# Adafruit_Feather_RP2040_DVI.net
KiCad netlist of a schematic drawn in EAGLE
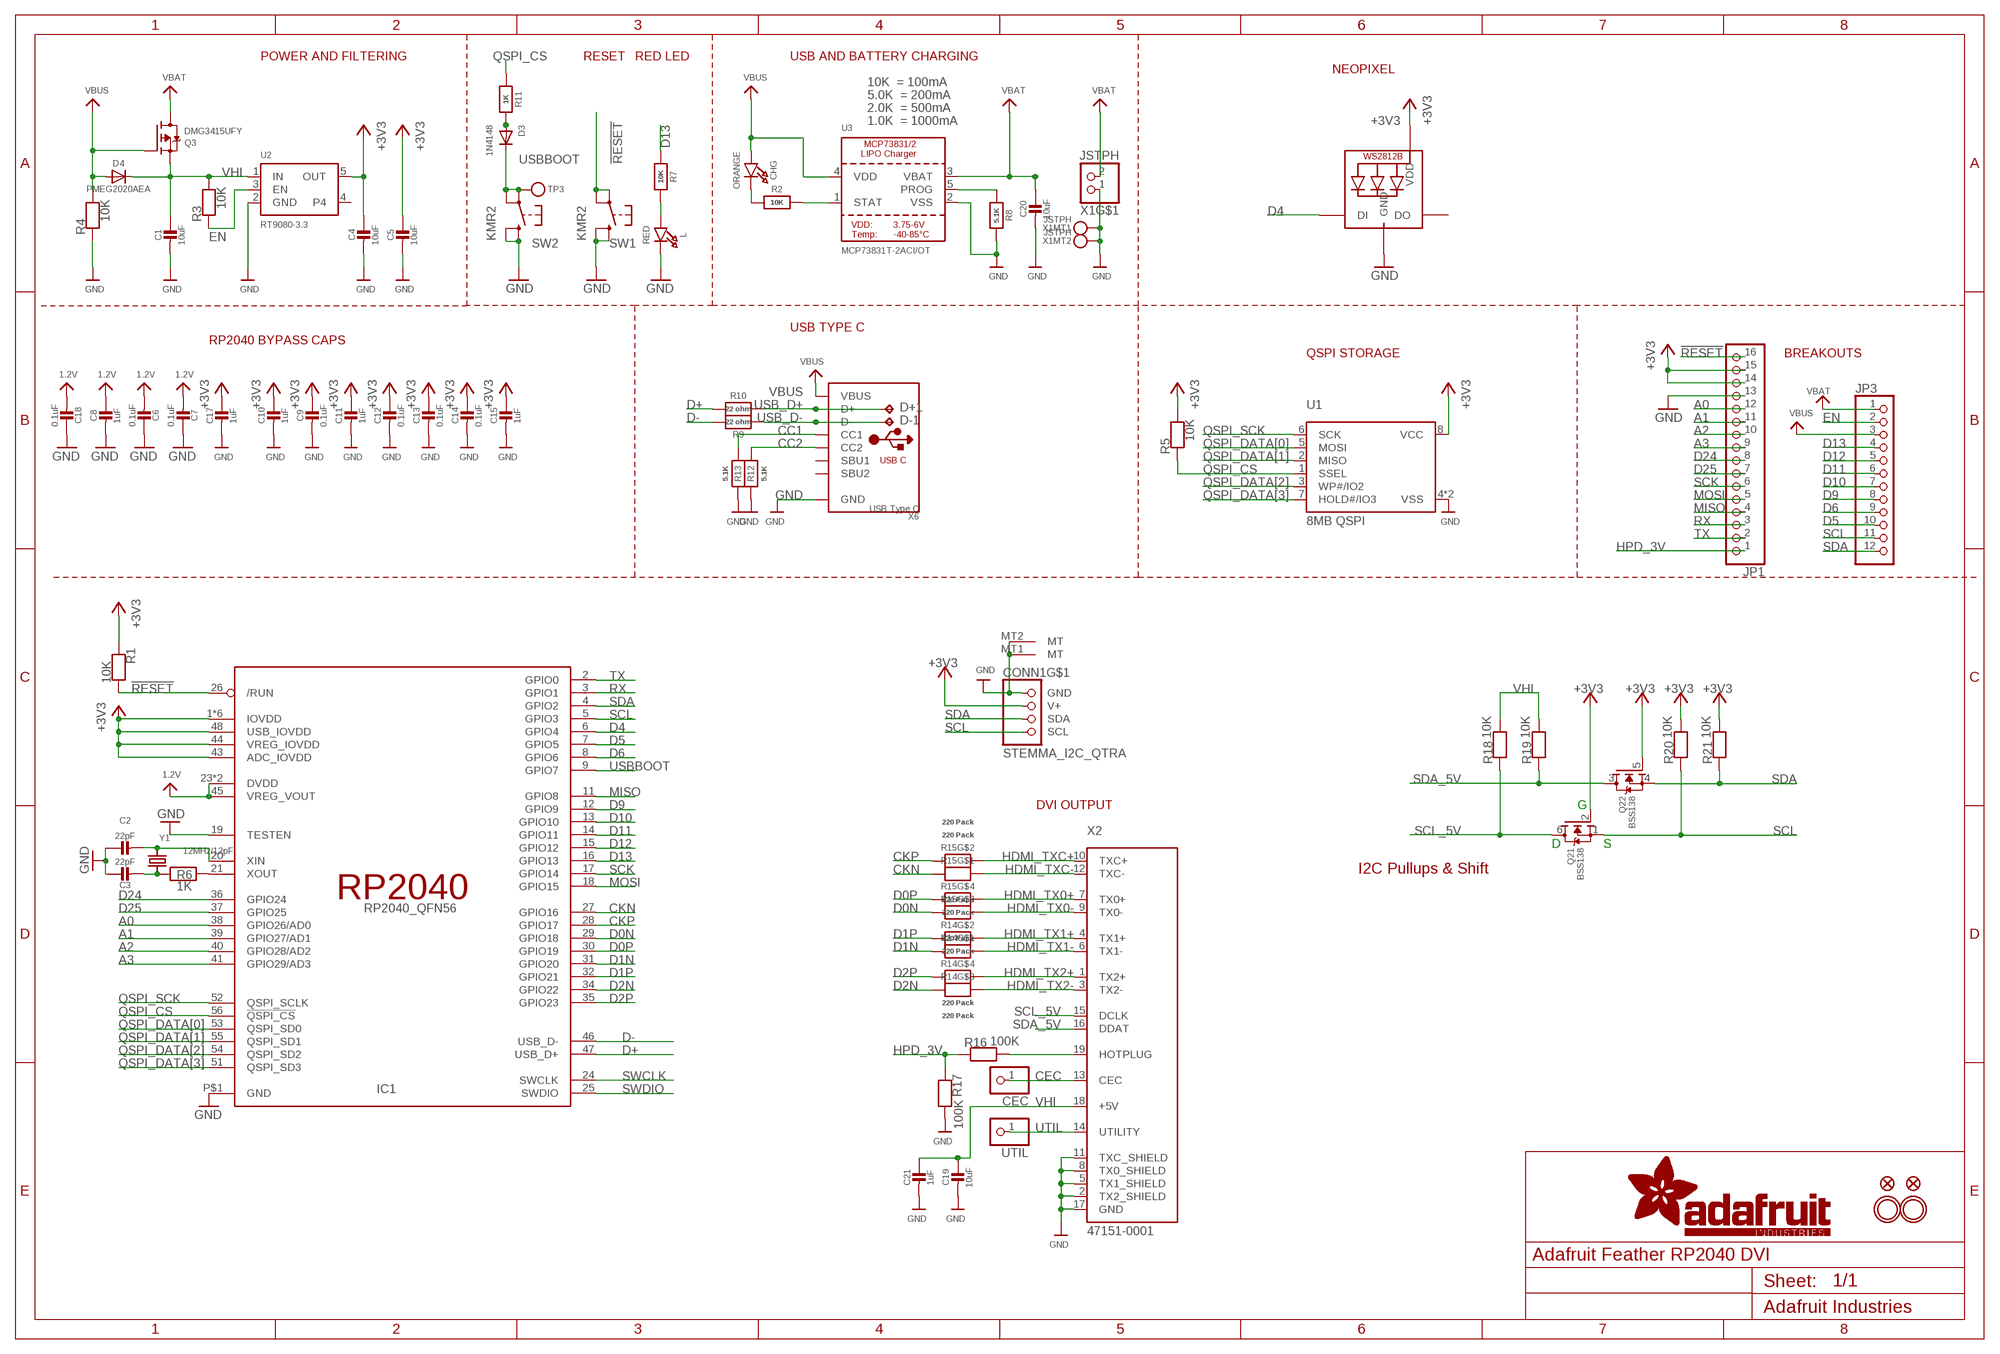
[diagram p0: schematic, sheet 1]

(export (version "E")
  (design (tool "Eeschema 10.0.6"))
  (components
    (comp (ref "C1")
      (value "10uF")
      (footprint "eagle-import:0805-NO")
      (libsource (lib "eagle-import") (part "CAP_CERAMIC0805-NOOUTLINE"))
    )
    (comp (ref "C2")
      (value "22pF")
      (footprint "eagle-import:_0402NO")
      (libsource (lib "eagle-import") (part "CAP_CERAMIC_0402NO"))
    )
    (comp (ref "C3")
      (value "22pF")
      (footprint "eagle-import:_0402NO")
      (libsource (lib "eagle-import") (part "CAP_CERAMIC_0402NO"))
    )
    (comp (ref "C4")
      (value "10uF")
      (footprint "eagle-import:0805-NO")
      (fields (field (name "REV") "A"))
      (libsource (lib "eagle-import") (part "CAP_CERAMIC0805-NOOUTLINE"))
    )
    (comp (ref "C5")
      (value "10uF")
      (footprint "eagle-import:0805-NO")
      (libsource (lib "eagle-import") (part "CAP_CERAMIC0805-NOOUTLINE"))
    )
    (comp (ref "C6")
      (value "0.1uF")
      (footprint "eagle-import:_0402NO")
      (libsource (lib "eagle-import") (part "CAP_CERAMIC_0402NO"))
    )
    (comp (ref "C7")
      (value "0.1uF")
      (footprint "eagle-import:_0402NO")
      (libsource (lib "eagle-import") (part "CAP_CERAMIC_0402NO"))
    )
    (comp (ref "C8")
      (value "1uF")
      (footprint "eagle-import:_0402NO")
      (libsource (lib "eagle-import") (part "CAP_CERAMIC_0402NO"))
    )
    (comp (ref "C9")
      (value "0.1uF")
      (footprint "eagle-import:_0402NO")
      (libsource (lib "eagle-import") (part "CAP_CERAMIC_0402NO"))
    )
    (comp (ref "C10")
      (value "1uF")
      (footprint "eagle-import:_0402NO")
      (libsource (lib "eagle-import") (part "CAP_CERAMIC_0402NO"))
    )
    (comp (ref "C11")
      (value "1uF")
      (footprint "eagle-import:_0402NO")
      (libsource (lib "eagle-import") (part "CAP_CERAMIC_0402NO"))
    )
    (comp (ref "C12")
      (value "0.1uF")
      (footprint "eagle-import:_0402NO")
      (libsource (lib "eagle-import") (part "CAP_CERAMIC_0402NO"))
    )
    (comp (ref "C13")
      (value "0.1uF")
      (footprint "eagle-import:_0402NO")
      (libsource (lib "eagle-import") (part "CAP_CERAMIC_0402NO"))
    )
    (comp (ref "C14")
      (value "0.1uF")
      (footprint "eagle-import:_0402NO")
      (libsource (lib "eagle-import") (part "CAP_CERAMIC_0402NO"))
    )
    (comp (ref "C15")
      (value "1uF")
      (footprint "eagle-import:_0402NO")
      (libsource (lib "eagle-import") (part "CAP_CERAMIC_0402NO"))
    )
    (comp (ref "C17")
      (value "1uF")
      (footprint "eagle-import:_0402NO")
      (libsource (lib "eagle-import") (part "CAP_CERAMIC_0402NO"))
    )
    (comp (ref "C18")
      (value "0.1uF")
      (footprint "eagle-import:_0402NO")
      (libsource (lib "eagle-import") (part "CAP_CERAMIC_0402NO"))
    )
    (comp (ref "C19")
      (value "10uF")
      (footprint "eagle-import:0805-NO")
      (fields (field (name "REV") "A"))
      (libsource (lib "eagle-import") (part "CAP_CERAMIC0805-NOOUTLINE"))
    )
    (comp (ref "C20")
      (value "10uF")
      (footprint "eagle-import:0805-NO")
      (libsource (lib "eagle-import") (part "CAP_CERAMIC0805-NOOUTLINE"))
    )
    (comp (ref "C21")
      (value "1uF")
      (footprint "eagle-import:_0402NO")
      (libsource (lib "eagle-import") (part "CAP_CERAMIC_0402NO"))
    )
    (comp (ref "CEC")
      (value "HEADER-1X1ROUND")
      (footprint "eagle-import:1X01_ROUND")
      (libsource (lib "eagle-import") (part "HEADER-1X1ROUND"))
    )
    (comp (ref "CHG")
      (value "ORANGE")
      (footprint "eagle-import:CHIPLED_0603_NOOUTLINE")
      (libsource (lib "eagle-import") (part "LED0603_NOOUTLINE"))
    )
    (comp (ref "CONN1")
      (value "STEMMA_I2C_QTRA")
      (footprint "eagle-import:JST_SH4_RA")
      (libsource (lib "eagle-import") (part "STEMMA_I2C_QTRA"))
    )
    (comp (ref "D+1")
      (value "TPB1,27")
      (footprint "eagle-import:B1,27")
      (libsource (lib "eagle-import") (part "TPB1,27"))
    )
    (comp (ref "D-1")
      (value "TPB1,27")
      (footprint "eagle-import:B1,27")
      (libsource (lib "eagle-import") (part "TPB1,27"))
    )
    (comp (ref "D3")
      (value "1N4148")
      (footprint "eagle-import:SOD-323F")
      (libsource (lib "eagle-import") (part "DIODESOD-323F"))
    )
    (comp (ref "D4")
      (value "PMEG2020AEA")
      (footprint "eagle-import:SOD-323F")
      (libsource (lib "eagle-import") (part "DIODESOD-323F"))
    )
    (comp (ref "IC1")
      (value "RP2040_QFN56")
      (footprint "eagle-import:QFN56_7MM_REDUCEDEPAD")
      (libsource (lib "eagle-import") (part "RP2040_QFN56"))
    )
    (comp (ref "JP1")
      (value "HEADER-1X16ROUND")
      (footprint "eagle-import:1X16_ROUND")
      (libsource (lib "eagle-import") (part "HEADER-1X16ROUND"))
    )
    (comp (ref "JP3")
      (value "HEADER-1X12")
      (footprint "eagle-import:1X12_ROUND")
      (libsource (lib "eagle-import") (part "HEADER-1X12"))
    )
    (comp (ref "L")
      (value "RED")
      (footprint "eagle-import:CHIPLED_0603_NOOUTLINE")
      (libsource (lib "eagle-import") (part "LED0603_NOOUTLINE"))
    )
    (comp (ref "LED1")
      (value "WS2812B_SK6805_1515")
      (footprint "eagle-import:SK6805_1515")
      (libsource (lib "eagle-import") (part "WS2812B_SK6805_1515"))
    )
    (comp (ref "Q2")
      (value "BSS138")
      (footprint "eagle-import:SOT363")
      (libsource (lib "eagle-import") (part "MOSFET-N_DUAL"))
    )
    (comp (ref "Q3")
      (value "DMG3415UFY")
      (footprint "eagle-import:DFN2015-3")
      (libsource (lib "eagle-import") (part "MOSFET-P_DFN2015"))
    )
    (comp (ref "R1")
      (value "10K")
      (footprint "eagle-import:_0402NO")
      (libsource (lib "eagle-import") (part "RESISTOR_0402NO"))
    )
    (comp (ref "R2")
      (value "10K")
      (footprint "eagle-import:_0402NO")
      (libsource (lib "eagle-import") (part "RESISTOR_0402NO"))
    )
    (comp (ref "R3")
      (value "10K")
      (footprint "eagle-import:_0402NO")
      (libsource (lib "eagle-import") (part "RESISTOR_0402NO"))
    )
    (comp (ref "R4")
      (value "10K")
      (footprint "eagle-import:_0402NO")
      (libsource (lib "eagle-import") (part "RESISTOR_0402NO"))
    )
    (comp (ref "R5")
      (value "10K")
      (footprint "eagle-import:_0402NO")
      (libsource (lib "eagle-import") (part "RESISTOR_0402NO"))
    )
    (comp (ref "R6")
      (value "1K")
      (footprint "eagle-import:_0402NO")
      (libsource (lib "eagle-import") (part "RESISTOR_0402NO"))
    )
    (comp (ref "R7")
      (value "10K")
      (footprint "eagle-import:_0402NO")
      (libsource (lib "eagle-import") (part "RESISTOR_0402NO"))
    )
    (comp (ref "R8")
      (value "5.1K")
      (footprint "eagle-import:_0402NO")
      (libsource (lib "eagle-import") (part "RESISTOR_0402NO"))
    )
    (comp (ref "R9")
      (value "22 ohm")
      (footprint "eagle-import:_0402NO")
      (libsource (lib "eagle-import") (part "RESISTOR_0402NO"))
    )
    (comp (ref "R10")
      (value "22 ohm")
      (footprint "eagle-import:_0402NO")
      (libsource (lib "eagle-import") (part "RESISTOR_0402NO"))
    )
    (comp (ref "R11")
      (value "1K")
      (footprint "eagle-import:_0402NO")
      (libsource (lib "eagle-import") (part "RESISTOR_0402NO"))
    )
    (comp (ref "R12")
      (value "5.1K")
      (footprint "eagle-import:_0402NO")
      (libsource (lib "eagle-import") (part "RESISTOR_0402NO"))
    )
    (comp (ref "R13")
      (value "5.1K")
      (footprint "eagle-import:_0402NO")
      (libsource (lib "eagle-import") (part "RESISTOR_0402NO"))
    )
    (comp (ref "R14")
      (value "220 Pack")
      (footprint "eagle-import:RESPACK_4X0603")
      (libsource (lib "eagle-import") (part "RESISTOR_4PACK"))
    )
    (comp (ref "R15")
      (value "220 Pack")
      (footprint "eagle-import:RESPACK_4X0603")
      (libsource (lib "eagle-import") (part "RESISTOR_4PACK"))
    )
    (comp (ref "R16")
      (value "100K")
      (footprint "eagle-import:_0402NO")
      (libsource (lib "eagle-import") (part "RESISTOR_0402NO"))
    )
    (comp (ref "R17")
      (value "100K")
      (footprint "eagle-import:_0402NO")
      (libsource (lib "eagle-import") (part "RESISTOR_0402NO"))
    )
    (comp (ref "R18")
      (value "10K")
      (footprint "eagle-import:_0402NO")
      (libsource (lib "eagle-import") (part "RESISTOR_0402NO"))
    )
    (comp (ref "R19")
      (value "10K")
      (footprint "eagle-import:_0402NO")
      (libsource (lib "eagle-import") (part "RESISTOR_0402NO"))
    )
    (comp (ref "R20")
      (value "10K")
      (footprint "eagle-import:_0402NO")
      (libsource (lib "eagle-import") (part "RESISTOR_0402NO"))
    )
    (comp (ref "R21")
      (value "10K")
      (footprint "eagle-import:_0402NO")
      (libsource (lib "eagle-import") (part "RESISTOR_0402NO"))
    )
    (comp (ref "SW1")
      (value "KMR2")
      (footprint "eagle-import:BTN_RKB2_4.6X2.8")
      (libsource (lib "eagle-import") (part "SWITCH_TACT_SMT_RKB2"))
    )
    (comp (ref "SW2")
      (value "KMR2")
      (footprint "eagle-import:BTN_RKB2_4.6X2.8")
      (libsource (lib "eagle-import") (part "SWITCH_TACT_SMT_RKB2"))
    )
    (comp (ref "TP3")
      (value "TESTPOINTROUND1.5MMNO")
      (footprint "eagle-import:TESTPOINT_ROUND_1.5MM_NO")
      (libsource (lib "eagle-import") (part "TESTPOINTROUND1.5MMNO"))
    )
    (comp (ref "U$31")
      (value "MOUNTINGHOLE2.5")
      (footprint "eagle-import:MOUNTINGHOLE_2.5_PLATED")
      (libsource (lib "eagle-import") (part "MOUNTINGHOLE2.5"))
    )
    (comp (ref "U$32")
      (value "MOUNTINGHOLE2.5")
      (footprint "eagle-import:MOUNTINGHOLE_2.5_PLATED")
      (libsource (lib "eagle-import") (part "MOUNTINGHOLE2.5"))
    )
    (comp (ref "U$34")
      (value "FIDUCIAL_1MM")
      (footprint "eagle-import:FIDUCIAL_1MM")
      (libsource (lib "eagle-import") (part "FIDUCIAL_1MM"))
    )
    (comp (ref "U$35")
      (value "FIDUCIAL_1MM")
      (footprint "eagle-import:FIDUCIAL_1MM")
      (libsource (lib "eagle-import") (part "FIDUCIAL_1MM"))
    )
    (comp (ref "U1")
      (value "8MB QSPI")
      (footprint "eagle-import:USON8_4X4")
      (libsource (lib "eagle-import") (part "SPIFLASH_8PIN_4X4"))
    )
    (comp (ref "U2")
      (value "RT9080-3.3")
      (footprint "eagle-import:SOT23-5")
      (fields (field (name "JLC_ROTATION") "0"))
      (libsource (lib "eagle-import") (part "VREG_SOT23-5"))
    )
    (comp (ref "U3")
      (value "MCP73831T-2ACI/OT")
      (footprint "eagle-import:SOT23-5")
      (libsource (lib "eagle-import") (part "MCP73831/2"))
    )
    (comp (ref "UTIL")
      (value "HEADER-1X1ROUND")
      (footprint "eagle-import:1X01_ROUND")
      (libsource (lib "eagle-import") (part "HEADER-1X1ROUND"))
    )
    (comp (ref "X1")
      (value "JSTPH")
      (footprint "eagle-import:JSTPH2_BATT")
      (libsource (lib "eagle-import") (part "CON_JST_PH_2PIN_MT_BATT"))
    )
    (comp (ref "X2")
      (value "47151-0001")
      (footprint "eagle-import:HDMI_MOLEX_47151-0001")
      (libsource (lib "eagle-import") (part "HDMI_MOLEX_47151"))
    )
    (comp (ref "X6")
      (value "USB Type C")
      (footprint "eagle-import:USB_C_CUSB31-CFM2AX-01-X")
      (libsource (lib "eagle-import") (part "USB_C"))
    )
    (comp (ref "Y1")
      (value "12MHz/12pF")
      (footprint "eagle-import:CRYSTAL_2.5X2")
      (libsource (lib "eagle-import") (part "CRYSTAL2.5X2.0"))
    )
  )
  (nets
    (net (code "1") (name "+3V3") (class "Default")
      (node (ref "C10") (pin "1") (pinfunction "1_1") (pintype "passive"))
      (node (ref "C11") (pin "1") (pinfunction "1_1") (pintype "passive"))
      (node (ref "C12") (pin "1") (pinfunction "1_1") (pintype "passive"))
      (node (ref "C13") (pin "1") (pinfunction "1_1") (pintype "passive"))
      (node (ref "C14") (pin "1") (pinfunction "1_1") (pintype "passive"))
      (node (ref "C15") (pin "1") (pinfunction "1_1") (pintype "passive"))
      (node (ref "C17") (pin "1") (pinfunction "1_1") (pintype "passive"))
      (node (ref "C4") (pin "1") (pinfunction "1_1") (pintype "passive"))
      (node (ref "C5") (pin "1") (pinfunction "1_1") (pintype "passive"))
      (node (ref "C9") (pin "1") (pinfunction "1_1") (pintype "passive"))
      (node (ref "CONN1") (pin "2") (pinfunction "V+_2") (pintype "passive"))
      (node (ref "IC1") (pin "1") (pinfunction "IOVDD_1") (pintype "power_in"))
      (node (ref "IC1") (pin "10") (pinfunction "IOVDD_10") (pintype "power_in"))
      (node (ref "IC1") (pin "22") (pinfunction "IOVDD_22") (pintype "power_in"))
      (node (ref "IC1") (pin "33") (pinfunction "IOVDD_33") (pintype "power_in"))
      (node (ref "IC1") (pin "42") (pinfunction "IOVDD_42") (pintype "power_in"))
      (node (ref "IC1") (pin "43") (pinfunction "ADC_IOVDD_43") (pintype "power_in"))
      (node (ref "IC1") (pin "44") (pinfunction "VREG_IOVDD_44") (pintype "power_in"))
      (node (ref "IC1") (pin "48") (pinfunction "USB_IOVDD_48") (pintype "power_in"))
      (node (ref "IC1") (pin "49") (pinfunction "IOVDD_49") (pintype "power_in"))
      (node (ref "JP1") (pin "14") (pinfunction "14_14") (pintype "passive"))
      (node (ref "JP1") (pin "15") (pinfunction "15_15") (pintype "passive"))
      (node (ref "LED1") (pin "2") (pinfunction "VDD_2") (pintype "power_in"))
      (node (ref "Q2") (pin "2") (pinfunction "G_2") (pintype "bidirectional"))
      (node (ref "Q2") (pin "5") (pinfunction "G_5") (pintype "bidirectional"))
      (node (ref "R1") (pin "1") (pinfunction "1_1") (pintype "passive"))
      (node (ref "R20") (pin "2") (pinfunction "2_2") (pintype "passive"))
      (node (ref "R21") (pin "2") (pinfunction "2_2") (pintype "passive"))
      (node (ref "R5") (pin "2") (pinfunction "2_2") (pintype "passive"))
      (node (ref "U1") (pin "8") (pinfunction "VCC_8") (pintype "bidirectional"))
      (node (ref "U2") (pin "5") (pinfunction "OUT_5") (pintype "power_in"))
    )
    (net (code "2") (name "/A0") (class "Default")
      (node (ref "IC1") (pin "38") (pinfunction "GPIO26/AD0_38") (pintype "bidirectional"))
      (node (ref "JP1") (pin "12") (pinfunction "12_12") (pintype "passive"))
    )
    (net (code "3") (name "/A1") (class "Default")
      (node (ref "IC1") (pin "39") (pinfunction "GPIO27/AD1_39") (pintype "bidirectional"))
      (node (ref "JP1") (pin "11") (pinfunction "11_11") (pintype "passive"))
    )
    (net (code "4") (name "/A2") (class "Default")
      (node (ref "IC1") (pin "40") (pinfunction "GPIO28/AD2_40") (pintype "bidirectional"))
      (node (ref "JP1") (pin "10") (pinfunction "10_10") (pintype "passive"))
    )
    (net (code "5") (name "/A3") (class "Default")
      (node (ref "IC1") (pin "41") (pinfunction "GPIO29/AD3_41") (pintype "bidirectional"))
      (node (ref "JP1") (pin "9") (pinfunction "9_9") (pintype "passive"))
    )
    (net (code "6") (name "/CC1") (class "Default")
      (node (ref "R13") (pin "2") (pinfunction "2_2") (pintype "passive"))
      (node (ref "X6") (pin "A5") (pinfunction "CC1_A5") (pintype "bidirectional"))
    )
    (net (code "7") (name "/CC2") (class "Default")
      (node (ref "R12") (pin "2") (pinfunction "2_2") (pintype "passive"))
      (node (ref "X6") (pin "B5") (pinfunction "CC2_B5") (pintype "bidirectional"))
    )
    (net (code "8") (name "/CEC") (class "Default")
      (node (ref "CEC") (pin "1") (pinfunction "1_1") (pintype "passive"))
      (node (ref "X2") (pin "13") (pinfunction "CEC_13") (pintype "bidirectional"))
    )
    (net (code "9") (name "/CKN") (class "Default")
      (node (ref "IC1") (pin "27") (pinfunction "GPIO16_27") (pintype "bidirectional"))
      (node (ref "R15") (pin "8") (pinfunction "2_8") (pintype "passive"))
    )
    (net (code "10") (name "/CKP") (class "Default")
      (node (ref "IC1") (pin "28") (pinfunction "GPIO17_28") (pintype "bidirectional"))
      (node (ref "R15") (pin "7") (pinfunction "2_7") (pintype "passive"))
    )
    (net (code "11") (name "/D+") (class "Default")
      (node (ref "IC1") (pin "47") (pinfunction "USB_D+_47") (pintype "bidirectional"))
      (node (ref "R10") (pin "2") (pinfunction "2_2") (pintype "passive"))
    )
    (net (code "12") (name "/D-") (class "Default")
      (node (ref "IC1") (pin "46") (pinfunction "USB_D-_46") (pintype "bidirectional"))
      (node (ref "R9") (pin "2") (pinfunction "2_2") (pintype "passive"))
    )
    (net (code "13") (name "/D0N") (class "Default")
      (node (ref "IC1") (pin "29") (pinfunction "GPIO18_29") (pintype "bidirectional"))
      (node (ref "R15") (pin "6") (pinfunction "2_6") (pintype "passive"))
    )
    (net (code "14") (name "/D0P") (class "Default")
      (node (ref "IC1") (pin "30") (pinfunction "GPIO19_30") (pintype "bidirectional"))
      (node (ref "R15") (pin "5") (pinfunction "2_5") (pintype "passive"))
    )
    (net (code "15") (name "/D1N") (class "Default")
      (node (ref "IC1") (pin "31") (pinfunction "GPIO20_31") (pintype "bidirectional"))
      (node (ref "R14") (pin "8") (pinfunction "2_8") (pintype "passive"))
    )
    (net (code "16") (name "/D1P") (class "Default")
      (node (ref "IC1") (pin "32") (pinfunction "GPIO21_32") (pintype "bidirectional"))
      (node (ref "R14") (pin "7") (pinfunction "2_7") (pintype "passive"))
    )
    (net (code "17") (name "/D2N") (class "Default")
      (node (ref "IC1") (pin "34") (pinfunction "GPIO22_34") (pintype "bidirectional"))
      (node (ref "R14") (pin "6") (pinfunction "2_6") (pintype "passive"))
    )
    (net (code "18") (name "/D2P") (class "Default")
      (node (ref "IC1") (pin "35") (pinfunction "GPIO23_35") (pintype "bidirectional"))
      (node (ref "R14") (pin "5") (pinfunction "2_5") (pintype "passive"))
    )
    (net (code "19") (name "/D4") (class "Default")
      (node (ref "IC1") (pin "6") (pinfunction "GPIO4_6") (pintype "bidirectional"))
      (node (ref "LED1") (pin "1") (pinfunction "DI_1") (pintype "input"))
    )
    (net (code "20") (name "/D5") (class "Default")
      (node (ref "IC1") (pin "7") (pinfunction "GPIO5_7") (pintype "bidirectional"))
      (node (ref "JP3") (pin "10") (pinfunction "10_10") (pintype "passive"))
    )
    (net (code "21") (name "/D6") (class "Default")
      (node (ref "IC1") (pin "8") (pinfunction "GPIO6_8") (pintype "bidirectional"))
      (node (ref "JP3") (pin "9") (pinfunction "9_9") (pintype "passive"))
    )
    (net (code "22") (name "/D9") (class "Default")
      (node (ref "IC1") (pin "12") (pinfunction "GPIO9_12") (pintype "bidirectional"))
      (node (ref "JP3") (pin "8") (pinfunction "8_8") (pintype "passive"))
    )
    (net (code "23") (name "/D10") (class "Default")
      (node (ref "IC1") (pin "13") (pinfunction "GPIO10_13") (pintype "bidirectional"))
      (node (ref "JP3") (pin "7") (pinfunction "7_7") (pintype "passive"))
    )
    (net (code "24") (name "/D11") (class "Default")
      (node (ref "IC1") (pin "14") (pinfunction "GPIO11_14") (pintype "bidirectional"))
      (node (ref "JP3") (pin "6") (pinfunction "6_6") (pintype "passive"))
    )
    (net (code "25") (name "/D12") (class "Default")
      (node (ref "IC1") (pin "15") (pinfunction "GPIO12_15") (pintype "bidirectional"))
      (node (ref "JP3") (pin "5") (pinfunction "5_5") (pintype "passive"))
    )
    (net (code "26") (name "/D13") (class "Default")
      (node (ref "IC1") (pin "16") (pinfunction "GPIO13_16") (pintype "bidirectional"))
      (node (ref "JP3") (pin "4") (pinfunction "4_4") (pintype "passive"))
      (node (ref "R7") (pin "1") (pinfunction "1_1") (pintype "passive"))
    )
    (net (code "27") (name "/D24") (class "Default")
      (node (ref "IC1") (pin "36") (pinfunction "GPIO24_36") (pintype "bidirectional"))
      (node (ref "JP1") (pin "8") (pinfunction "8_8") (pintype "passive"))
    )
    (net (code "28") (name "/D25") (class "Default")
      (node (ref "IC1") (pin "37") (pinfunction "GPIO25_37") (pintype "bidirectional"))
      (node (ref "JP1") (pin "7") (pinfunction "7_7") (pintype "passive"))
    )
    (net (code "29") (name "/EN") (class "Default")
      (node (ref "JP3") (pin "2") (pinfunction "2_2") (pintype "passive"))
      (node (ref "R3") (pin "1") (pinfunction "1_1") (pintype "passive"))
      (node (ref "U2") (pin "3") (pinfunction "EN_3") (pintype "input"))
    )
    (net (code "30") (name "/HDMI_TX0+") (class "Default")
      (node (ref "R15") (pin "4") (pinfunction "1_4") (pintype "passive"))
      (node (ref "X2") (pin "7") (pinfunction "TX0+_7") (pintype "bidirectional"))
    )
    (net (code "31") (name "/HDMI_TX0-") (class "Default")
      (node (ref "R15") (pin "3") (pinfunction "1_3") (pintype "passive"))
      (node (ref "X2") (pin "9") (pinfunction "TX0-_9") (pintype "bidirectional"))
    )
    (net (code "32") (name "/HDMI_TX1+") (class "Default")
      (node (ref "R14") (pin "2") (pinfunction "1_2") (pintype "passive"))
      (node (ref "X2") (pin "4") (pinfunction "TX1+_4") (pintype "bidirectional"))
    )
    (net (code "33") (name "/HDMI_TX1-") (class "Default")
      (node (ref "R14") (pin "1") (pinfunction "1_1") (pintype "passive"))
      (node (ref "X2") (pin "6") (pinfunction "TX1-_6") (pintype "bidirectional"))
    )
    (net (code "34") (name "/HDMI_TX2+") (class "Default")
      (node (ref "R14") (pin "4") (pinfunction "1_4") (pintype "passive"))
      (node (ref "X2") (pin "1") (pinfunction "TX2+_1") (pintype "bidirectional"))
    )
    (net (code "35") (name "/HDMI_TX2-") (class "Default")
      (node (ref "R14") (pin "3") (pinfunction "1_3") (pintype "passive"))
      (node (ref "X2") (pin "3") (pinfunction "TX2-_3") (pintype "bidirectional"))
    )
    (net (code "36") (name "/HDMI_TXC+") (class "Default")
      (node (ref "R15") (pin "2") (pinfunction "1_2") (pintype "passive"))
      (node (ref "X2") (pin "10") (pinfunction "TXC+_10") (pintype "bidirectional"))
    )
    (net (code "37") (name "/HDMI_TXC-") (class "Default")
      (node (ref "R15") (pin "1") (pinfunction "1_1") (pintype "passive"))
      (node (ref "X2") (pin "12") (pinfunction "TXC-_12") (pintype "bidirectional"))
    )
    (net (code "38") (name "/HPD_3V") (class "Default")
      (node (ref "JP1") (pin "1") (pinfunction "1_1") (pintype "passive"))
      (node (ref "R16") (pin "1") (pinfunction "1_1") (pintype "passive"))
      (node (ref "R17") (pin "1") (pinfunction "1_1") (pintype "passive"))
    )
    (net (code "39") (name "/MISO") (class "Default")
      (node (ref "IC1") (pin "11") (pinfunction "GPIO8_11") (pintype "bidirectional"))
      (node (ref "JP1") (pin "4") (pinfunction "4_4") (pintype "passive"))
    )
    (net (code "40") (name "/MOSI") (class "Default")
      (node (ref "IC1") (pin "18") (pinfunction "GPIO15_18") (pintype "bidirectional"))
      (node (ref "JP1") (pin "5") (pinfunction "5_5") (pintype "passive"))
    )
    (net (code "41") (name "/QSPI_CS") (class "Default")
      (node (ref "IC1") (pin "56") (pinfunction "~{QSPI_CS}_56") (pintype "bidirectional"))
      (node (ref "R11") (pin "1") (pinfunction "1_1") (pintype "passive"))
      (node (ref "R5") (pin "1") (pinfunction "1_1") (pintype "passive"))
      (node (ref "U1") (pin "1") (pinfunction "SSEL_1") (pintype "bidirectional"))
    )
    (net (code "42") (name "/QSPI_DATA[0]") (class "Default")
      (node (ref "IC1") (pin "53") (pinfunction "QSPI_SD0_53") (pintype "bidirectional"))
      (node (ref "U1") (pin "5") (pinfunction "MOSI_5") (pintype "bidirectional"))
    )
    (net (code "43") (name "/QSPI_DATA[1]") (class "Default")
      (node (ref "IC1") (pin "55") (pinfunction "QSPI_SD1_55") (pintype "bidirectional"))
      (node (ref "U1") (pin "2") (pinfunction "MISO_2") (pintype "bidirectional"))
    )
    (net (code "44") (name "/QSPI_DATA[2]") (class "Default")
      (node (ref "IC1") (pin "54") (pinfunction "QSPI_SD2_54") (pintype "bidirectional"))
      (node (ref "U1") (pin "3") (pinfunction "WP#/IO2_3") (pintype "bidirectional"))
    )
    (net (code "45") (name "/QSPI_DATA[3]") (class "Default")
      (node (ref "IC1") (pin "51") (pinfunction "QSPI_SD3_51") (pintype "bidirectional"))
      (node (ref "U1") (pin "7") (pinfunction "HOLD#/IO3_7") (pintype "bidirectional"))
    )
    (net (code "46") (name "/QSPI_SCK") (class "Default")
      (node (ref "IC1") (pin "52") (pinfunction "QSPI_SCLK_52") (pintype "bidirectional"))
      (node (ref "U1") (pin "6") (pinfunction "SCK_6") (pintype "bidirectional"))
    )
    (net (code "47") (name "/RX") (class "Default")
      (node (ref "IC1") (pin "3") (pinfunction "GPIO1_3") (pintype "bidirectional"))
      (node (ref "JP1") (pin "3") (pinfunction "3_3") (pintype "passive"))
    )
    (net (code "48") (name "/SCK") (class "Default")
      (node (ref "IC1") (pin "17") (pinfunction "GPIO14_17") (pintype "bidirectional"))
      (node (ref "JP1") (pin "6") (pinfunction "6_6") (pintype "passive"))
    )
    (net (code "49") (name "/SCL") (class "Default")
      (node (ref "CONN1") (pin "4") (pinfunction "SCL_4") (pintype "passive"))
      (node (ref "IC1") (pin "5") (pinfunction "GPIO3_5") (pintype "bidirectional"))
      (node (ref "JP3") (pin "11") (pinfunction "11_11") (pintype "passive"))
      (node (ref "Q2") (pin "1") (pinfunction "S_1") (pintype "bidirectional"))
      (node (ref "R20") (pin "1") (pinfunction "1_1") (pintype "passive"))
    )
    (net (code "50") (name "/SCL_5V") (class "Default")
      (node (ref "Q2") (pin "6") (pinfunction "D_6") (pintype "bidirectional"))
      (node (ref "R18") (pin "1") (pinfunction "1_1") (pintype "passive"))
      (node (ref "X2") (pin "15") (pinfunction "DCLK_15") (pintype "bidirectional"))
    )
    (net (code "51") (name "/SDA") (class "Default")
      (node (ref "CONN1") (pin "3") (pinfunction "SDA_3") (pintype "passive"))
      (node (ref "IC1") (pin "4") (pinfunction "GPIO2_4") (pintype "bidirectional"))
      (node (ref "JP3") (pin "12") (pinfunction "12_12") (pintype "passive"))
      (node (ref "Q2") (pin "4") (pinfunction "S_4") (pintype "bidirectional"))
      (node (ref "R21") (pin "1") (pinfunction "1_1") (pintype "passive"))
    )
    (net (code "52") (name "/SDA_5V") (class "Default")
      (node (ref "Q2") (pin "3") (pinfunction "D_3") (pintype "bidirectional"))
      (node (ref "R19") (pin "1") (pinfunction "1_1") (pintype "passive"))
      (node (ref "X2") (pin "16") (pinfunction "DDAT_16") (pintype "bidirectional"))
    )
    (net (code "53") (name "/SWCLK") (class "Default")
      (node (ref "IC1") (pin "24") (pinfunction "SWCLK_24") (pintype "bidirectional"))
    )
    (net (code "54") (name "/SWDIO") (class "Default")
      (node (ref "IC1") (pin "25") (pinfunction "SWDIO_25") (pintype "bidirectional"))
    )
    (net (code "55") (name "/TX") (class "Default")
      (node (ref "IC1") (pin "2") (pinfunction "GPIO0_2") (pintype "bidirectional"))
      (node (ref "JP1") (pin "2") (pinfunction "2_2") (pintype "passive"))
    )
    (net (code "56") (name "/USBBOOT") (class "Default")
      (node (ref "D3") (pin "C") (pinfunction "C_C") (pintype "passive"))
      (node (ref "IC1") (pin "9") (pinfunction "GPIO7_9") (pintype "bidirectional"))
      (node (ref "SW2") (pin "A") (pinfunction "P_A") (pintype "passive"))
      (node (ref "SW2") (pin "A'") (pinfunction "P1_A'") (pintype "passive"))
      (node (ref "TP3") (pin "P$1") (pinfunction "P$1_P$1") (pintype "bidirectional"))
    )
    (net (code "57") (name "/USB_D+") (class "Default")
      (node (ref "D+1") (pin "TP") (pinfunction "TP_TP") (pintype "input"))
      (node (ref "R10") (pin "1") (pinfunction "1_1") (pintype "passive"))
      (node (ref "X6") (pin "A6") (pinfunction "D+_A6") (pintype "bidirectional"))
      (node (ref "X6") (pin "B6") (pinfunction "D+_B6") (pintype "bidirectional"))
    )
    (net (code "58") (name "/USB_D-") (class "Default")
      (node (ref "D-1") (pin "TP") (pinfunction "TP_TP") (pintype "input"))
      (node (ref "R9") (pin "1") (pinfunction "1_1") (pintype "passive"))
      (node (ref "X6") (pin "A7") (pinfunction "D-_A7") (pintype "bidirectional"))
      (node (ref "X6") (pin "B7") (pinfunction "D-_B7") (pintype "bidirectional"))
    )
    (net (code "59") (name "/UTIL") (class "Default")
      (node (ref "UTIL") (pin "1") (pinfunction "1_1") (pintype "passive"))
      (node (ref "X2") (pin "14") (pinfunction "UTILITY_14") (pintype "bidirectional"))
    )
    (net (code "60") (name "/VHI") (class "Default")
      (node (ref "C1") (pin "1") (pinfunction "1_1") (pintype "passive"))
      (node (ref "C19") (pin "1") (pinfunction "1_1") (pintype "passive"))
      (node (ref "C21") (pin "1") (pinfunction "1_1") (pintype "passive"))
      (node (ref "D4") (pin "C") (pinfunction "C_C") (pintype "passive"))
      (node (ref "Q3") (pin "2") (pinfunction "S_2") (pintype "passive"))
      (node (ref "R18") (pin "2") (pinfunction "2_2") (pintype "passive"))
      (node (ref "R19") (pin "2") (pinfunction "2_2") (pintype "passive"))
      (node (ref "R3") (pin "2") (pinfunction "2_2") (pintype "passive"))
      (node (ref "U2") (pin "1") (pinfunction "IN_1") (pintype "power_in"))
      (node (ref "X2") (pin "18") (pinfunction "+5V_18") (pintype "power_in"))
    )
    (net (code "61") (name "/~{RESET}") (class "Default")
      (node (ref "IC1") (pin "26") (pinfunction "/RUN_26") (pintype "bidirectional"))
      (node (ref "JP1") (pin "16") (pinfunction "16_16") (pintype "passive"))
      (node (ref "R1") (pin "2") (pinfunction "2_2") (pintype "passive"))
      (node (ref "SW1") (pin "A") (pinfunction "P_A") (pintype "passive"))
      (node (ref "SW1") (pin "A'") (pinfunction "P1_A'") (pintype "passive"))
    )
    (net (code "62") (name "1.2V") (class "Default")
      (node (ref "C18") (pin "2") (pinfunction "2_2") (pintype "passive"))
      (node (ref "C6") (pin "2") (pinfunction "2_2") (pintype "passive"))
      (node (ref "C7") (pin "2") (pinfunction "2_2") (pintype "passive"))
      (node (ref "C8") (pin "1") (pinfunction "1_1") (pintype "passive"))
      (node (ref "IC1") (pin "23") (pinfunction "DVDD_23") (pintype "power_in"))
      (node (ref "IC1") (pin "45") (pinfunction "VREG_VOUT_45") (pintype "power_in"))
      (node (ref "IC1") (pin "50") (pinfunction "DVDD_50") (pintype "power_in"))
    )
    (net (code "63") (name "GND") (class "Default")
      (node (ref "C1") (pin "2") (pinfunction "2_2") (pintype "passive"))
      (node (ref "C10") (pin "2") (pinfunction "2_2") (pintype "passive"))
      (node (ref "C11") (pin "2") (pinfunction "2_2") (pintype "passive"))
      (node (ref "C12") (pin "2") (pinfunction "2_2") (pintype "passive"))
      (node (ref "C13") (pin "2") (pinfunction "2_2") (pintype "passive"))
      (node (ref "C14") (pin "2") (pinfunction "2_2") (pintype "passive"))
      (node (ref "C15") (pin "2") (pinfunction "2_2") (pintype "passive"))
      (node (ref "C17") (pin "2") (pinfunction "2_2") (pintype "passive"))
      (node (ref "C18") (pin "1") (pinfunction "1_1") (pintype "passive"))
      (node (ref "C19") (pin "2") (pinfunction "2_2") (pintype "passive"))
      (node (ref "C2") (pin "1") (pinfunction "1_1") (pintype "passive"))
      (node (ref "C20") (pin "2") (pinfunction "2_2") (pintype "passive"))
      (node (ref "C21") (pin "2") (pinfunction "2_2") (pintype "passive"))
      (node (ref "C3") (pin "1") (pinfunction "1_1") (pintype "passive"))
      (node (ref "C4") (pin "2") (pinfunction "2_2") (pintype "passive"))
      (node (ref "C5") (pin "2") (pinfunction "2_2") (pintype "passive"))
      (node (ref "C6") (pin "1") (pinfunction "1_1") (pintype "passive"))
      (node (ref "C7") (pin "1") (pinfunction "1_1") (pintype "passive"))
      (node (ref "C8") (pin "2") (pinfunction "2_2") (pintype "passive"))
      (node (ref "C9") (pin "2") (pinfunction "2_2") (pintype "passive"))
      (node (ref "CONN1") (pin "1") (pinfunction "GND_1") (pintype "passive"))
      (node (ref "CONN1") (pin "MT1") (pinfunction "MT_MT1") (pintype "bidirectional"))
      (node (ref "CONN1") (pin "MT2") (pinfunction "MT_MT2") (pintype "bidirectional"))
      (node (ref "IC1") (pin "19") (pinfunction "TESTEN_19") (pintype "input"))
      (node (ref "IC1") (pin "P$1") (pinfunction "GND_P$1") (pintype "power_in"))
      (node (ref "JP1") (pin "13") (pinfunction "13_13") (pintype "passive"))
      (node (ref "L") (pin "C") (pinfunction "C_C") (pintype "passive"))
      (node (ref "LED1") (pin "4") (pinfunction "GND_4") (pintype "power_in"))
      (node (ref "R12") (pin "1") (pinfunction "1_1") (pintype "passive"))
      (node (ref "R13") (pin "1") (pinfunction "1_1") (pintype "passive"))
      (node (ref "R17") (pin "2") (pinfunction "2_2") (pintype "passive"))
      (node (ref "R4") (pin "1") (pinfunction "1_1") (pintype "passive"))
      (node (ref "R8") (pin "2") (pinfunction "2_2") (pintype "passive"))
      (node (ref "SW1") (pin "B") (pinfunction "S_B") (pintype "passive"))
      (node (ref "SW1") (pin "B'") (pinfunction "S1_B'") (pintype "passive"))
      (node (ref "SW2") (pin "B") (pinfunction "S_B") (pintype "passive"))
      (node (ref "SW2") (pin "B'") (pinfunction "S1_B'") (pintype "passive"))
      (node (ref "U1") (pin "4") (pinfunction "VSS_4") (pintype "bidirectional"))
      (node (ref "U1") (pin "PAD") (pinfunction "VSS_PAD") (pintype "bidirectional"))
      (node (ref "U2") (pin "2") (pinfunction "GND_2") (pintype "power_in"))
      (node (ref "U3") (pin "2") (pinfunction "VSS_2") (pintype "power_in"))
      (node (ref "X1") (pin "1") (pinfunction "1_1") (pintype "passive"))
      (node (ref "X1") (pin "NC1") (pinfunction "P$1_NC1") (pintype "bidirectional"))
      (node (ref "X1") (pin "NC2") (pinfunction "P$1_NC2") (pintype "bidirectional"))
      (node (ref "X2") (pin "11") (pinfunction "TXC_SHIELD_11") (pintype "power_in"))
      (node (ref "X2") (pin "17") (pinfunction "GND_17") (pintype "power_in"))
      (node (ref "X2") (pin "2") (pinfunction "TX2_SHIELD_2") (pintype "power_in"))
      (node (ref "X2") (pin "5") (pinfunction "TX1_SHIELD_5") (pintype "power_in"))
      (node (ref "X2") (pin "8") (pinfunction "TX0_SHIELD_8") (pintype "power_in"))
      (node (ref "X6") (pin "A1B12") (pinfunction "GND_A1B12") (pintype "power_in"))
      (node (ref "X6") (pin "B1A12") (pinfunction "GND_B1A12") (pintype "power_in"))
    )
    (net (code "64") (name "Net-(C3-Pad2)") (class "Default")
      (node (ref "C3") (pin "2") (pinfunction "2_2") (pintype "passive"))
      (node (ref "R6") (pin "1") (pinfunction "1_1") (pintype "passive"))
      (node (ref "Y1") (pin "1") (pinfunction "1_1") (pintype "passive"))
    )
    (net (code "65") (name "Net-(CHG-PadC)") (class "Default")
      (node (ref "CHG") (pin "C") (pinfunction "C_C") (pintype "passive"))
      (node (ref "R2") (pin "1") (pinfunction "1_1") (pintype "passive"))
    )
    (net (code "66") (name "Net-(D3-PadA)") (class "Default")
      (node (ref "D3") (pin "A") (pinfunction "A_A") (pintype "passive"))
      (node (ref "R11") (pin "2") (pinfunction "2_2") (pintype "passive"))
    )
    (net (code "67") (name "Net-(IC1-XIN)") (class "Default")
      (node (ref "C2") (pin "2") (pinfunction "2_2") (pintype "passive"))
      (node (ref "IC1") (pin "20") (pinfunction "XIN_20") (pintype "input"))
      (node (ref "Y1") (pin "3") (pinfunction "2_3") (pintype "passive"))
    )
    (net (code "68") (name "Net-(IC1-XOUT)") (class "Default")
      (node (ref "IC1") (pin "21") (pinfunction "XOUT_21") (pintype "output"))
      (node (ref "R6") (pin "2") (pinfunction "2_2") (pintype "passive"))
    )
    (net (code "69") (name "Net-(L-PadA)") (class "Default")
      (node (ref "L") (pin "A") (pinfunction "A_A") (pintype "passive"))
      (node (ref "R7") (pin "2") (pinfunction "2_2") (pintype "passive"))
    )
    (net (code "70") (name "Net-(U3-PROG)") (class "Default")
      (node (ref "R8") (pin "1") (pinfunction "1_1") (pintype "passive"))
      (node (ref "U3") (pin "5") (pinfunction "PROG_5") (pintype "input"))
    )
    (net (code "71") (name "Net-(U3-STAT)") (class "Default")
      (node (ref "R2") (pin "2") (pinfunction "2_2") (pintype "passive"))
      (node (ref "U3") (pin "1") (pinfunction "STAT_1") (pintype "output"))
    )
    (net (code "72") (name "Net-(X2A-HOTPLUG)") (class "Default")
      (node (ref "R16") (pin "2") (pinfunction "2_2") (pintype "passive"))
      (node (ref "X2") (pin "19") (pinfunction "HOTPLUG_19") (pintype "bidirectional"))
    )
    (net (code "73") (name "VBAT") (class "Default")
      (node (ref "C20") (pin "1") (pinfunction "1_1") (pintype "passive"))
      (node (ref "JP3") (pin "1") (pinfunction "1_1") (pintype "passive"))
      (node (ref "Q3") (pin "3") (pinfunction "D_3") (pintype "passive"))
      (node (ref "U3") (pin "3") (pinfunction "VBAT_3") (pintype "power_in"))
      (node (ref "X1") (pin "2") (pinfunction "2_2") (pintype "passive"))
    )
    (net (code "74") (name "VBUS") (class "Default")
      (node (ref "CHG") (pin "A") (pinfunction "A_A") (pintype "passive"))
      (node (ref "D4") (pin "A") (pinfunction "A_A") (pintype "passive"))
      (node (ref "JP3") (pin "3") (pinfunction "3_3") (pintype "passive"))
      (node (ref "Q3") (pin "1") (pinfunction "G_1") (pintype "passive"))
      (node (ref "R4") (pin "2") (pinfunction "2_2") (pintype "passive"))
      (node (ref "U3") (pin "4") (pinfunction "VDD_4") (pintype "power_in"))
      (node (ref "X6") (pin "A4B9") (pinfunction "VBUS_A4B9") (pintype "power_in"))
      (node (ref "X6") (pin "B4A9") (pinfunction "VBUS_B4A9") (pintype "power_in"))
    )
    (net (code "75") (name "unconnected-(LED1-DO-Pad3)") (class "Default")
      (node (ref "LED1") (pin "3") (pinfunction "DO_3") (pintype "output"))
    )
    (net (code "76") (name "unconnected-(U2-P4-Pad4)") (class "Default")
      (node (ref "U2") (pin "4") (pinfunction "P4_4") (pintype "bidirectional"))
    )
    (net (code "77") (name "unconnected-(X6-SBU1-PadA8)") (class "Default")
      (node (ref "X6") (pin "A8") (pinfunction "SBU1_A8") (pintype "bidirectional"))
    )
    (net (code "78") (name "unconnected-(X6-SBU2-PadB8)") (class "Default")
      (node (ref "X6") (pin "B8") (pinfunction "SBU2_B8") (pintype "bidirectional"))
    )
  )
)
